# LVMCU.net
KiCad netlist of a schematic drawn in Altium Designer
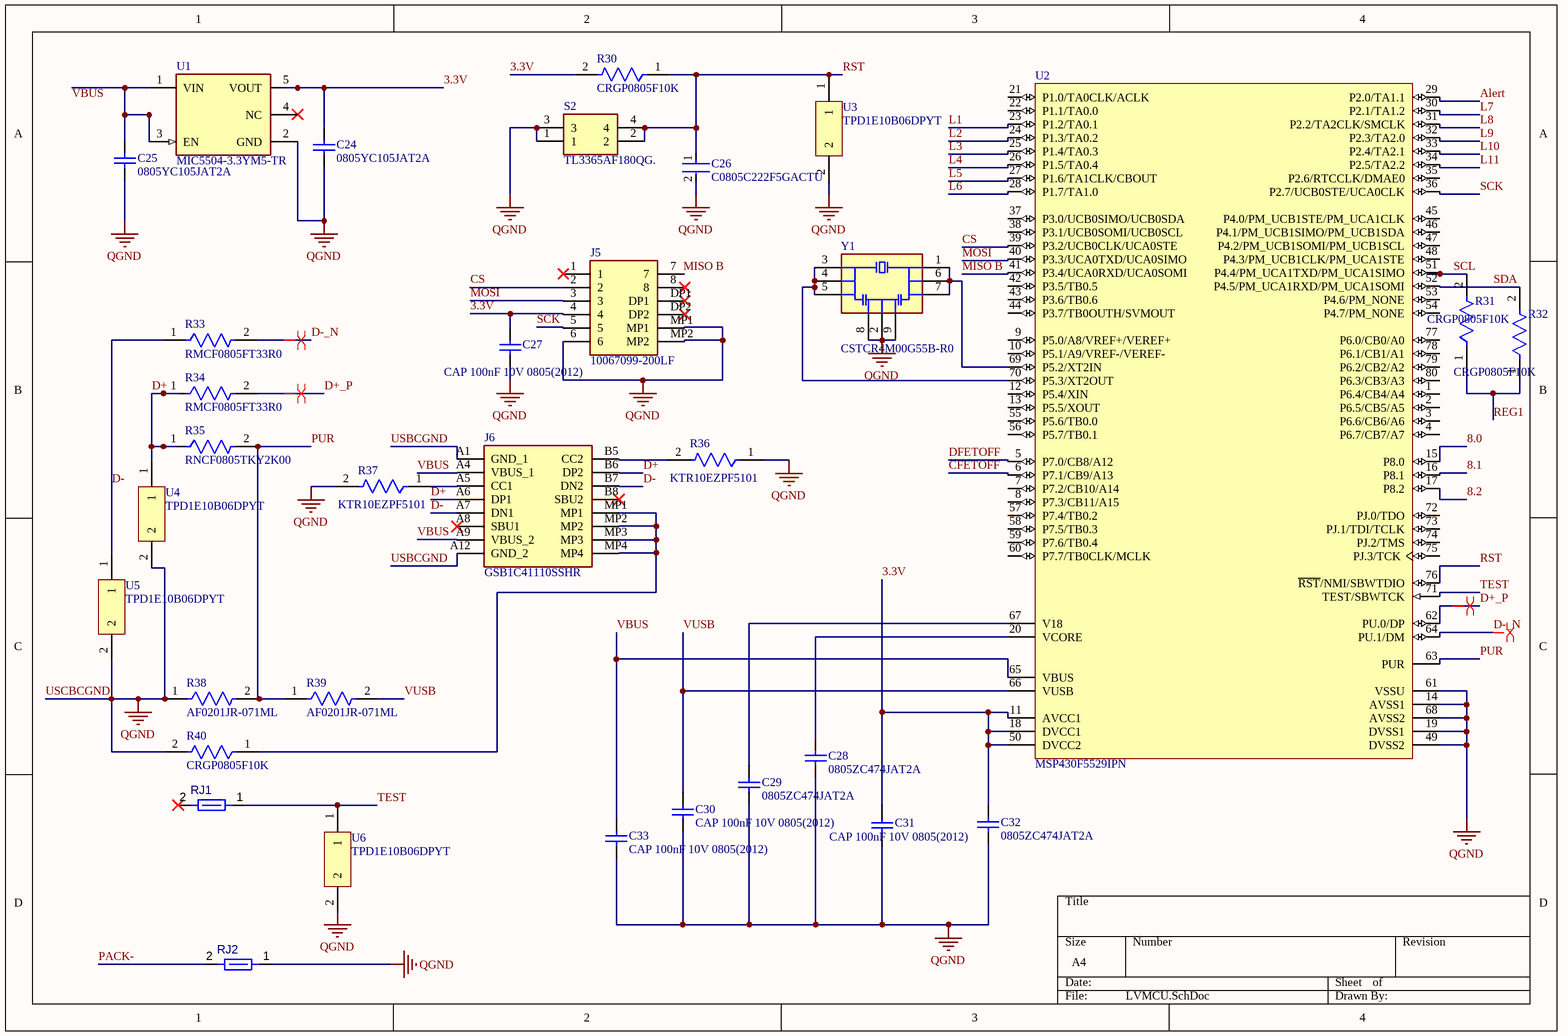
[diagram p0: LVMCU.SchDoc]

(export (version "E")
  (design (tool "Eeschema 10.0.6"))
  (components
    (comp (ref "C24")
      (value "0805YC105JAT2A")
      (footprint "CAPC2013X140X50ML20T25")
      (fields (field (name "MANUFACTURER") "AVX Interconnect / Elco"))
      (libsource (lib "Altium Content Vault") (part "CAP"))
    )
    (comp (ref "C25")
      (value "0805YC105JAT2A")
      (footprint "CAPC2013X140X50ML20T25")
      (fields (field (name "MANUFACTURER") "AVX Interconnect / Elco"))
      (libsource (lib "Altium Content Vault") (part "CAP"))
    )
    (comp (ref "C26")
      (value "C0805C222F5GACTU")
      (footprint "FP-C0805C-DN-MFG")
      (description "CAP CER 2200PF 50V C0G/NP0 0805")
      (fields
        (field (name "OCTOPART") "https://octopart.com/c0805c222f5gactu-kemet-17301038")
        (field (name "TOLERANCE") "0.01")
      )
      (libsource (lib "Altium Content Vault") (part "b4654b650e69147ec39a6b967a45e02"))
    )
    (comp (ref "C27")
      (value "CAP 100nF 10V 0805(2012)")
      (footprint "CAPC0805(2012)100_M")
      (description "CAP 100nF 10V ±5% 0805 (2012 Metric) Thickness 1mm SMD")
      (fields (field (name "TOLERANCE") "Â±5%"))
      (libsource (lib "Altium Content Vault") (part "CAP"))
    )
    (comp (ref "C28")
      (value "0805ZC474JAT2A")
      (footprint "CAPC2013X140X50LL20T25")
      (libsource (lib "Altium Content Vault") (part "CAP"))
    )
    (comp (ref "C29")
      (value "0805ZC474JAT2A")
      (footprint "CAPC2013X140X50LL20T25")
      (libsource (lib "Altium Content Vault") (part "CAP"))
    )
    (comp (ref "C30")
      (value "CAP 100nF 10V 0805(2012)")
      (footprint "CAPC0805(2012)100_M")
      (description "CAP 100nF 10V ±5% 0805 (2012 Metric) Thickness 1mm SMD")
      (fields (field (name "TOLERANCE") "Â±5%"))
      (libsource (lib "Altium Content Vault") (part "CAP"))
    )
    (comp (ref "C31")
      (value "CAP 100nF 10V 0805(2012)")
      (footprint "CAPC0805(2012)100_M")
      (description "CAP 100nF 10V ±5% 0805 (2012 Metric) Thickness 1mm SMD")
      (fields (field (name "TOLERANCE") "Â±5%"))
      (libsource (lib "Altium Content Vault") (part "CAP"))
    )
    (comp (ref "C32")
      (value "0805ZC474JAT2A")
      (footprint "CAPC2013X140X50LL20T25")
      (libsource (lib "Altium Content Vault") (part "CAP"))
    )
    (comp (ref "C33")
      (value "CAP 100nF 10V 0805(2012)")
      (footprint "CAPC0805(2012)100_M")
      (description "CAP 100nF 10V ±5% 0805 (2012 Metric) Thickness 1mm SMD")
      (fields (field (name "TOLERANCE") "Â±5%"))
      (libsource (lib "Altium Content Vault") (part "CAP"))
    )
    (comp (ref "J5")
      (value "10067099-200LF")
      (footprint "SamacSys:10067099200LF")
      (description "Connector")
      (fields (field (name "MOUSER PART NUMBER") "649-10067099-200LF"))
      (libsource (lib "*") (part "10067099-200LF"))
    )
    (comp (ref "J6")
      (value "GSB1C41110SSHR")
      (footprint "SamacSys:GSB1C41110SSHR")
      (description "Connector")
      (libsource (lib "*") (part "GSB1C41110SSHR"))
    )
    (comp (ref "R30")
      (value "CRGP0805F10K")
      (footprint "FP-CRGP0805-IPC_C")
      (description "CRGP0805 10KΩ 0.33W ±100ppm/°C 1% 150V")
      (fields (field (name "OCTOPART") "https://octopart.com/crgp0805f10k-te+connectivity-91018782"))
      (libsource (lib "Altium Content Vault") (part "1029c3af85768c4190bb7ad29bc67b5"))
    )
    (comp (ref "R31")
      (value "CRGP0805F10K")
      (footprint "FP-CRGP0805-IPC_C")
      (description "CRGP0805 10KΩ 0.33W ±100ppm/°C 1% 150V")
      (fields (field (name "OCTOPART") "https://octopart.com/crgp0805f10k-te+connectivity-91018782"))
      (libsource (lib "Altium Content Vault") (part "1029c3af85768c4190bb7ad29bc67b5"))
    )
    (comp (ref "R32")
      (value "CRGP0805F10K")
      (footprint "FP-CRGP0805-IPC_C")
      (description "CRGP0805 10KΩ 0.33W ±100ppm/°C 1% 150V")
      (fields (field (name "OCTOPART") "https://octopart.com/crgp0805f10k-te+connectivity-91018782"))
      (libsource (lib "Altium Content Vault") (part "1029c3af85768c4190bb7ad29bc67b5"))
    )
    (comp (ref "R33")
      (value "RMCF0805FT33R0")
      (footprint "FP-RMCF0805-MFG")
      (description "33Ω ±1% 0.125W 0805 Thick Film Chip Resistor AEC-Q200 compliant")
      (fields (field (name "TOLERANCE") "1%"))
      (libsource (lib "Altium Content Vault") (part "1029c3af85768c4190bb7ad29bc67b5"))
    )
    (comp (ref "R34")
      (value "RMCF0805FT33R0")
      (footprint "FP-RMCF0805-MFG")
      (description "33Ω ±1% 0.125W 0805 Thick Film Chip Resistor AEC-Q200 compliant")
      (fields (field (name "TOLERANCE") "1%"))
      (libsource (lib "Altium Content Vault") (part "1029c3af85768c4190bb7ad29bc67b5"))
    )
    (comp (ref "R35")
      (value "RNCF0805TKY2K00")
      (footprint "FP-RNCF0805-MFG")
      (description "RES 2K OHM 0.01% 1/8W 0805")
      (fields (field (name "TOLERANCE") "0.01%"))
      (libsource (lib "Altium Content Vault") (part "1029c3af85768c4190bb7ad29bc67b5"))
    )
    (comp (ref "R36")
      (value "KTR10EZPF5101")
      (footprint "FP-KTR10-MFG")
      (description "Res Thick Film 0805 5.1kΩ 1% 0.125W ±100ppm/°C Automotive Paper T/R")
      (fields (field (name "TOLERANCE") "1%"))
      (libsource (lib "Altium Content Vault") (part "1029c3af85768c4190bb7ad29bc67b5"))
    )
    (comp (ref "R37")
      (value "KTR10EZPF5101")
      (footprint "FP-KTR10-MFG")
      (description "Res Thick Film 0805 5.1kΩ 1% 0.125W ±100ppm/°C Automotive Paper T/R")
      (fields (field (name "TOLERANCE") "1%"))
      (libsource (lib "Altium Content Vault") (part "1029c3af85768c4190bb7ad29bc67b5"))
    )
    (comp (ref "R38")
      (value "AF0201JR-071ML")
      (footprint "FP-AF0201-IPC_B")
      (description "Anti-Sulfurated Chip Resistors Automotive Grade 1MΩ 5% 200ppm/°C 0201")
      (fields (field (name "TOLERANCE") "5%"))
      (libsource (lib "Altium Content Vault") (part "1029c3af85768c4190bb7ad29bc67b5"))
    )
    (comp (ref "R39")
      (value "AF0201JR-071ML")
      (footprint "FP-AF0201-IPC_B")
      (description "Anti-Sulfurated Chip Resistors Automotive Grade 1MΩ 5% 200ppm/°C 0201")
      (fields (field (name "TOLERANCE") "5%"))
      (libsource (lib "Altium Content Vault") (part "1029c3af85768c4190bb7ad29bc67b5"))
    )
    (comp (ref "R40")
      (value "CRGP0805F10K")
      (footprint "FP-CRGP0805-IPC_C")
      (description "CRGP0805 10KΩ 0.33W ±100ppm/°C 1% 150V")
      (fields (field (name "OCTOPART") "https://octopart.com/crgp0805f10k-te+connectivity-91018782"))
      (libsource (lib "Altium Content Vault") (part "1029c3af85768c4190bb7ad29bc67b5"))
    )
    (comp (ref "RJ1")
      (value "Net Tie 0.6x1.4mm")
      (footprint "SHORT10_8MIL-FP")
      (libsource (lib "Toronto Met Formula Racing") (part "CMP-00022-00002-2"))
    )
    (comp (ref "RJ2")
      (value "Net Tie 0.6x1.4mm")
      (footprint "SHORT10_8MIL-FP")
      (libsource (lib "Toronto Met Formula Racing") (part "CMP-00022-00002-2"))
    )
    (comp (ref "S2")
      (value "TL3365AF180QG.")
      (footprint "SamacSys:TL3365AF180QG")
      (description "Switch")
      (libsource (lib "*") (part "TL3365AF180QG."))
    )
    (comp (ref "U1")
      (value "MIC5504-3.3YM5-TR")
      (footprint "FP-SOT23-5LD-PL-1-MFG")
      (description "IC REG LINEAR 3.3V 300MA SOT23-5")
      (libsource (lib "Altium Content Vault") (part "96048095611b4a9579e1e315950d302"))
    )
    (comp (ref "U2")
      (value "MSP430F5529IPN")
      (footprint "PN0080A_L")
      (libsource (lib "Altium Content Vault") (part "TI-MSP430F552X_A-PN80"))
    )
    (comp (ref "U3")
      (value "TPD1E10B06DPYT")
      (footprint "DPY0002A_L")
      (libsource (lib "Altium Content Vault") (part "TI-TPD1E10B06-X2SON_DPY-2"))
    )
    (comp (ref "U4")
      (value "TPD1E10B06DPYT")
      (footprint "DPY0002A_L")
      (libsource (lib "Altium Content Vault") (part "TI-TPD1E10B06-X2SON_DPY-2"))
    )
    (comp (ref "U5")
      (value "TPD1E10B06DPYT")
      (footprint "DPY0002A_L")
      (libsource (lib "Altium Content Vault") (part "TI-TPD1E10B06-X2SON_DPY-2"))
    )
    (comp (ref "U6")
      (value "TPD1E10B06DPYT")
      (footprint "DPY0002A_L")
      (libsource (lib "Altium Content Vault") (part "TI-TPD1E10B06-X2SON_DPY-2"))
    )
    (comp (ref "Y1")
      (value "CSTCR4M00G55B-R0")
      (footprint "SamacSys:CSTCR4M00G55B95R0")
      (description "Crystal or Oscillator")
      (fields (field (name "MOUSER PART NUMBER") "81-CSTCR4M00G55B-R0"))
      (libsource (lib "*") (part "CSTCR4M00G55B-R0"))
    )
  )
  (nets
    (net (code "1") (name "/3.3V") (class "Default")
      (node (ref "C24") (pin "2") (pinfunction "2_2") (pintype "passive"))
      (node (ref "C27") (pin "2") (pinfunction "2_2") (pintype "passive"))
      (node (ref "C31") (pin "2") (pinfunction "2_2") (pintype "passive"))
      (node (ref "C32") (pin "2") (pinfunction "2_2") (pintype "passive"))
      (node (ref "J5") (pin "4") (pinfunction "4_4") (pintype "passive"))
      (node (ref "R30") (pin "2") (pinfunction "2_2") (pintype "passive"))
      (node (ref "U1") (pin "5") (pinfunction "VOUT_5") (pintype "power_in"))
      (node (ref "U2") (pin "11") (pinfunction "AVCC1_11") (pintype "power_in"))
      (node (ref "U2") (pin "18") (pinfunction "DVCC1_18") (pintype "power_in"))
      (node (ref "U2") (pin "50") (pinfunction "DVCC2_50") (pintype "power_in"))
    )
    (net (code "2") (name "/8.0") (class "Default")
      (node (ref "U2") (pin "15") (pinfunction "P8.0_15") (pintype "bidirectional"))
    )
    (net (code "3") (name "/8.1") (class "Default")
      (node (ref "U2") (pin "16") (pinfunction "P8.1_16") (pintype "bidirectional"))
    )
    (net (code "4") (name "/8.2") (class "Default")
      (node (ref "U2") (pin "17") (pinfunction "P8.2_17") (pintype "bidirectional"))
    )
    (net (code "5") (name "/Alert") (class "Default")
      (node (ref "U2") (pin "29") (pinfunction "P2.0/TA1.1_29") (pintype "bidirectional"))
    )
    (net (code "6") (name "/CFETOFF") (class "Default")
      (node (ref "U2") (pin "6") (pinfunction "P7.1/CB9/A13_6") (pintype "bidirectional"))
    )
    (net (code "7") (name "/CS") (class "Default")
      (node (ref "J5") (pin "2") (pinfunction "2_2") (pintype "passive"))
      (node (ref "U2") (pin "39") (pinfunction "P3.2/UCB0CLK/UCA0STE_39") (pintype "bidirectional"))
    )
    (net (code "8") (name "/D+") (class "Default")
      (node (ref "J6") (pin "A6") (pinfunction "DP1_A6") (pintype "passive"))
      (node (ref "J6") (pin "B6") (pinfunction "DP2_B6") (pintype "passive"))
      (node (ref "R34") (pin "1") (pinfunction "1_1") (pintype "passive"))
      (node (ref "R35") (pin "1") (pinfunction "1_1") (pintype "passive"))
      (node (ref "U4") (pin "1") (pinfunction "1_1") (pintype "passive"))
    )
    (net (code "9") (name "/D+_P") (class "Default")
      (node (ref "R34") (pin "2") (pinfunction "2_2") (pintype "passive"))
      (node (ref "U2") (pin "62") (pinfunction "PU.0/DP_62") (pintype "bidirectional"))
    )
    (net (code "10") (name "/D-") (class "Default")
      (node (ref "J6") (pin "A7") (pinfunction "DN1_A7") (pintype "passive"))
      (node (ref "J6") (pin "B7") (pinfunction "DN2_B7") (pintype "passive"))
      (node (ref "R33") (pin "1") (pinfunction "1_1") (pintype "passive"))
      (node (ref "U5") (pin "1") (pinfunction "1_1") (pintype "passive"))
    )
    (net (code "11") (name "/D-_N") (class "Default")
      (node (ref "R33") (pin "2") (pinfunction "2_2") (pintype "passive"))
      (node (ref "U2") (pin "64") (pinfunction "PU.1/DM_64") (pintype "bidirectional"))
    )
    (net (code "12") (name "/DFETOFF") (class "Default")
      (node (ref "U2") (pin "5") (pinfunction "P7.0/CB8/A12_5") (pintype "bidirectional"))
    )
    (net (code "13") (name "/L1") (class "Default")
      (node (ref "U2") (pin "23") (pinfunction "P1.2/TA0.1_23") (pintype "bidirectional"))
    )
    (net (code "14") (name "/L2") (class "Default")
      (node (ref "U2") (pin "24") (pinfunction "P1.3/TA0.2_24") (pintype "bidirectional"))
    )
    (net (code "15") (name "/L3") (class "Default")
      (node (ref "U2") (pin "25") (pinfunction "P1.4/TA0.3_25") (pintype "bidirectional"))
    )
    (net (code "16") (name "/L4") (class "Default")
      (node (ref "U2") (pin "26") (pinfunction "P1.5/TA0.4_26") (pintype "bidirectional"))
    )
    (net (code "17") (name "/L5") (class "Default")
      (node (ref "U2") (pin "27") (pinfunction "P1.6/TA1CLK/CBOUT_27") (pintype "bidirectional"))
    )
    (net (code "18") (name "/L6") (class "Default")
      (node (ref "U2") (pin "28") (pinfunction "P1.7/TA1.0_28") (pintype "bidirectional"))
    )
    (net (code "19") (name "/L7") (class "Default")
      (node (ref "U2") (pin "30") (pinfunction "P2.1/TA1.2_30") (pintype "bidirectional"))
    )
    (net (code "20") (name "/L8") (class "Default")
      (node (ref "U2") (pin "31") (pinfunction "P2.2/TA2CLK/SMCLK_31") (pintype "bidirectional"))
    )
    (net (code "21") (name "/L9") (class "Default")
      (node (ref "U2") (pin "32") (pinfunction "P2.3/TA2.0_32") (pintype "bidirectional"))
    )
    (net (code "22") (name "/L10") (class "Default")
      (node (ref "U2") (pin "33") (pinfunction "P2.4/TA2.1_33") (pintype "bidirectional"))
    )
    (net (code "23") (name "/L11") (class "Default")
      (node (ref "U2") (pin "34") (pinfunction "P2.5/TA2.2_34") (pintype "bidirectional"))
    )
    (net (code "24") (name "/MISO B") (class "Default")
      (node (ref "J5") (pin "7") (pinfunction "7_7") (pintype "passive"))
      (node (ref "U2") (pin "41") (pinfunction "P3.4/UCA0RXD/UCA0SOMI_41") (pintype "bidirectional"))
    )
    (net (code "25") (name "/MOSI") (class "Default")
      (node (ref "J5") (pin "3") (pinfunction "3_3") (pintype "passive"))
      (node (ref "U2") (pin "40") (pinfunction "P3.3/UCA0TXD/UCA0SIMO_40") (pintype "bidirectional"))
    )
    (net (code "26") (name "/PACK-") (class "Default")
      (node (ref "RJ2") (pin "2") (pinfunction "2_2") (pintype "passive"))
    )
    (net (code "27") (name "/PUR") (class "Default")
      (node (ref "R35") (pin "2") (pinfunction "2_2") (pintype "passive"))
      (node (ref "R38") (pin "2") (pinfunction "2_2") (pintype "passive"))
      (node (ref "R39") (pin "1") (pinfunction "1_1") (pintype "passive"))
      (node (ref "U2") (pin "63") (pinfunction "PUR_63") (pintype "passive"))
    )
    (net (code "28") (name "/REG1") (class "Default")
      (node (ref "R31") (pin "1") (pinfunction "1_1") (pintype "passive"))
      (node (ref "R32") (pin "1") (pinfunction "1_1") (pintype "passive"))
    )
    (net (code "29") (name "/RST") (class "Default")
      (node (ref "C26") (pin "1") (pinfunction "1_1") (pintype "passive"))
      (node (ref "R30") (pin "1") (pinfunction "1_1") (pintype "passive"))
      (node (ref "S2") (pin "2") (pinfunction "2_2") (pintype "passive"))
      (node (ref "S2") (pin "4") (pinfunction "4_4") (pintype "passive"))
      (node (ref "U2") (pin "76") (pinfunction "~{RST}/NMI/SBWTDIO_76") (pintype "bidirectional"))
      (node (ref "U3") (pin "1") (pinfunction "1_1") (pintype "passive"))
    )
    (net (code "30") (name "/SCK") (class "Default")
      (node (ref "J5") (pin "5") (pinfunction "5_5") (pintype "passive"))
      (node (ref "U2") (pin "36") (pinfunction "P2.7/UCB0STE/UCA0CLK_36") (pintype "bidirectional"))
    )
    (net (code "31") (name "/SCL") (class "Default")
      (node (ref "R31") (pin "2") (pinfunction "2_2") (pintype "passive"))
      (node (ref "U2") (pin "51") (pinfunction "P4.4/PM_UCA1TXD/PM_UCA1SIMO_51") (pintype "bidirectional"))
    )
    (net (code "32") (name "/SDA") (class "Default")
      (node (ref "R32") (pin "2") (pinfunction "2_2") (pintype "passive"))
      (node (ref "U2") (pin "52") (pinfunction "P4.5/PM_UCA1RXD/PM_UCA1SOMI_52") (pintype "bidirectional"))
    )
    (net (code "33") (name "/TEST") (class "Default")
      (node (ref "RJ1") (pin "1") (pinfunction "1_1") (pintype "passive"))
      (node (ref "U2") (pin "71") (pinfunction "TEST/SBWTCK_71") (pintype "input"))
      (node (ref "U6") (pin "1") (pinfunction "1_1") (pintype "passive"))
    )
    (net (code "34") (name "/USBCGND") (class "Default")
      (node (ref "J6") (pin "A1") (pinfunction "GND_1_A1") (pintype "passive"))
      (node (ref "J6") (pin "A12") (pinfunction "GND_2_A12") (pintype "passive"))
    )
    (net (code "35") (name "/VBUS") (class "Default")
      (node (ref "C33") (pin "2") (pinfunction "2_2") (pintype "passive"))
      (node (ref "J6") (pin "A4") (pinfunction "VBUS_1_A4") (pintype "passive"))
      (node (ref "J6") (pin "A9") (pinfunction "VBUS_2_A9") (pintype "passive"))
      (node (ref "U2") (pin "65") (pinfunction "VBUS_65") (pintype "power_in"))
    )
    (net (code "36") (name "/VUSB") (class "Default")
      (node (ref "C30") (pin "2") (pinfunction "2_2") (pintype "passive"))
      (node (ref "R39") (pin "2") (pinfunction "2_2") (pintype "passive"))
      (node (ref "U2") (pin "66") (pinfunction "VUSB_66") (pintype "power_in"))
    )
    (net (code "37") (name "Net-(J6-CC1)") (class "Default")
      (node (ref "J6") (pin "A5") (pinfunction "CC1_A5") (pintype "passive"))
      (node (ref "R37") (pin "1") (pinfunction "1_1") (pintype "passive"))
    )
    (net (code "38") (name "Net-(J6-CC2)") (class "Default")
      (node (ref "J6") (pin "B5") (pinfunction "CC2_B5") (pintype "passive"))
      (node (ref "R36") (pin "2") (pinfunction "2_2") (pintype "passive"))
    )
    (net (code "39") (name "Net-(J6-PadMP1)") (class "Default")
      (node (ref "J6") (pin "MP1") (pinfunction "MP1_MP1") (pintype "passive"))
      (node (ref "J6") (pin "MP2") (pinfunction "MP2_MP2") (pintype "passive"))
      (node (ref "J6") (pin "MP3") (pinfunction "MP3_MP3") (pintype "passive"))
      (node (ref "J6") (pin "MP4") (pinfunction "MP4_MP4") (pintype "passive"))
      (node (ref "R40") (pin "1") (pinfunction "1_1") (pintype "passive"))
    )
    (net (code "40") (name "Net-(U1-EN)") (class "Default")
      (node (ref "C25") (pin "2") (pinfunction "2_2") (pintype "passive"))
      (node (ref "U1") (pin "1") (pinfunction "VIN_1") (pintype "power_in"))
      (node (ref "U1") (pin "3") (pinfunction "EN_3") (pintype "input"))
    )
    (net (code "41") (name "Net-(U2-P5.2{slash}XT2IN)") (class "Default")
      (node (ref "U2") (pin "69") (pinfunction "P5.2/XT2IN_69") (pintype "bidirectional"))
      (node (ref "Y1") (pin "1") (pinfunction "INPUT_1_1") (pintype "passive"))
      (node (ref "Y1") (pin "6") (pinfunction "OUTPUT_2_6") (pintype "passive"))
      (node (ref "Y1") (pin "7") (pinfunction "INPUT_3_7") (pintype "passive"))
    )
    (net (code "42") (name "Net-(U2-P5.3{slash}XT2OUT)") (class "Default")
      (node (ref "U2") (pin "70") (pinfunction "P5.3/XT2OUT_70") (pintype "bidirectional"))
      (node (ref "Y1") (pin "3") (pinfunction "OUTPUT_1_3") (pintype "passive"))
      (node (ref "Y1") (pin "4") (pinfunction "INPUT_2_4") (pintype "passive"))
      (node (ref "Y1") (pin "5") (pinfunction "GND_2_5") (pintype "passive"))
    )
    (net (code "43") (name "Net-(U2-V18)") (class "Default")
      (node (ref "C29") (pin "2") (pinfunction "2_2") (pintype "passive"))
      (node (ref "U2") (pin "67") (pinfunction "V18_67") (pintype "passive"))
    )
    (net (code "44") (name "Net-(U2-VCORE)") (class "Default")
      (node (ref "C28") (pin "2") (pinfunction "2_2") (pintype "passive"))
      (node (ref "U2") (pin "20") (pinfunction "VCORE_20") (pintype "passive"))
    )
    (net (code "45") (name "QGND") (class "Default")
      (node (ref "C24") (pin "1") (pinfunction "1_1") (pintype "passive"))
      (node (ref "C25") (pin "1") (pinfunction "1_1") (pintype "passive"))
      (node (ref "C26") (pin "2") (pinfunction "2_2") (pintype "passive"))
      (node (ref "C27") (pin "1") (pinfunction "1_1") (pintype "passive"))
      (node (ref "C28") (pin "1") (pinfunction "1_1") (pintype "passive"))
      (node (ref "C29") (pin "1") (pinfunction "1_1") (pintype "passive"))
      (node (ref "C30") (pin "1") (pinfunction "1_1") (pintype "passive"))
      (node (ref "C31") (pin "1") (pinfunction "1_1") (pintype "passive"))
      (node (ref "C32") (pin "1") (pinfunction "1_1") (pintype "passive"))
      (node (ref "C33") (pin "1") (pinfunction "1_1") (pintype "passive"))
      (node (ref "J5") (pin "6") (pinfunction "6_6") (pintype "passive"))
      (node (ref "J5") (pin "MP1") (pinfunction "MP1_MP1") (pintype "passive"))
      (node (ref "J5") (pin "MP2") (pinfunction "MP2_MP2") (pintype "passive"))
      (node (ref "R36") (pin "1") (pinfunction "1_1") (pintype "passive"))
      (node (ref "R37") (pin "2") (pinfunction "2_2") (pintype "passive"))
      (node (ref "R38") (pin "1") (pinfunction "1_1") (pintype "passive"))
      (node (ref "R40") (pin "2") (pinfunction "2_2") (pintype "passive"))
      (node (ref "RJ2") (pin "1") (pinfunction "1_1") (pintype "passive"))
      (node (ref "S2") (pin "1") (pinfunction "1_1") (pintype "passive"))
      (node (ref "S2") (pin "3") (pinfunction "3_3") (pintype "passive"))
      (node (ref "U1") (pin "2") (pinfunction "GND_2") (pintype "power_in"))
      (node (ref "U2") (pin "14") (pinfunction "AVSS1_14") (pintype "power_in"))
      (node (ref "U2") (pin "19") (pinfunction "DVSS1_19") (pintype "power_in"))
      (node (ref "U2") (pin "49") (pinfunction "DVSS2_49") (pintype "power_in"))
      (node (ref "U2") (pin "61") (pinfunction "VSSU_61") (pintype "power_in"))
      (node (ref "U2") (pin "68") (pinfunction "AVSS2_68") (pintype "power_in"))
      (node (ref "U3") (pin "2") (pinfunction "2_2") (pintype "passive"))
      (node (ref "U4") (pin "2") (pinfunction "2_2") (pintype "passive"))
      (node (ref "U5") (pin "2") (pinfunction "2_2") (pintype "passive"))
      (node (ref "U6") (pin "2") (pinfunction "2_2") (pintype "passive"))
      (node (ref "Y1") (pin "2") (pinfunction "GND_1_2") (pintype "passive"))
      (node (ref "Y1") (pin "8") (pinfunction "GND_3_8") (pintype "passive"))
      (node (ref "Y1") (pin "9") (pinfunction "OUTPUT_3_9") (pintype "passive"))
    )
    (net (code "46") (name "unconnected-(J5-Pad1)") (class "Default")
      (node (ref "J5") (pin "1") (pinfunction "1_1") (pintype "passive+no_connect"))
    )
    (net (code "47") (name "unconnected-(J5-Pad8)") (class "Default")
      (node (ref "J5") (pin "8") (pinfunction "8_8") (pintype "passive+no_connect"))
    )
    (net (code "48") (name "unconnected-(J5-PadDP1)") (class "Default")
      (node (ref "J5") (pin "DP1") (pinfunction "DP1_DP1") (pintype "passive+no_connect"))
    )
    (net (code "49") (name "unconnected-(J5-PadDP2)") (class "Default")
      (node (ref "J5") (pin "DP2") (pinfunction "DP2_DP2") (pintype "passive+no_connect"))
    )
    (net (code "50") (name "unconnected-(J6-SBU1-PadA8)") (class "Default")
      (node (ref "J6") (pin "A8") (pinfunction "SBU1_A8") (pintype "passive+no_connect"))
    )
    (net (code "51") (name "unconnected-(J6-SBU2-PadB8)") (class "Default")
      (node (ref "J6") (pin "B8") (pinfunction "SBU2_B8") (pintype "passive+no_connect"))
    )
    (net (code "52") (name "unconnected-(RJ1-Pad2)") (class "Default")
      (node (ref "RJ1") (pin "2") (pinfunction "2_2") (pintype "passive+no_connect"))
    )
    (net (code "53") (name "unconnected-(U1-NC-Pad4)") (class "Default")
      (node (ref "U1") (pin "4") (pinfunction "NC_4") (pintype "passive"))
    )
    (net (code "54") (name "unconnected-(U2-P1.0{slash}TA0CLK{slash}ACLK-Pad21)") (class "Default")
      (node (ref "U2") (pin "21") (pinfunction "P1.0/TA0CLK/ACLK_21") (pintype "bidirectional"))
    )
    (net (code "55") (name "unconnected-(U2-P1.1{slash}TA0.0-Pad22)") (class "Default")
      (node (ref "U2") (pin "22") (pinfunction "P1.1/TA0.0_22") (pintype "bidirectional"))
    )
    (net (code "56") (name "unconnected-(U2-P2.6{slash}RTCCLK{slash}DMAE0-Pad35)") (class "Default")
      (node (ref "U2") (pin "35") (pinfunction "P2.6/RTCCLK/DMAE0_35") (pintype "bidirectional"))
    )
    (net (code "57") (name "unconnected-(U2-P3.0{slash}UCB0SIMO{slash}UCB0SDA-Pad37)") (class "Default")
      (node (ref "U2") (pin "37") (pinfunction "P3.0/UCB0SIMO/UCB0SDA_37") (pintype "bidirectional"))
    )
    (net (code "58") (name "unconnected-(U2-P3.1{slash}UCB0SOMI{slash}UCB0SCL-Pad38)") (class "Default")
      (node (ref "U2") (pin "38") (pinfunction "P3.1/UCB0SOMI/UCB0SCL_38") (pintype "bidirectional"))
    )
    (net (code "59") (name "unconnected-(U2-P3.5{slash}TB0.5-Pad42)") (class "Default")
      (node (ref "U2") (pin "42") (pinfunction "P3.5/TB0.5_42") (pintype "bidirectional"))
    )
    (net (code "60") (name "unconnected-(U2-P3.6{slash}TB0.6-Pad43)") (class "Default")
      (node (ref "U2") (pin "43") (pinfunction "P3.6/TB0.6_43") (pintype "bidirectional"))
    )
    (net (code "61") (name "unconnected-(U2-P3.7{slash}TB0OUTH{slash}SVMOUT-Pad44)") (class "Default")
      (node (ref "U2") (pin "44") (pinfunction "P3.7/TB0OUTH/SVMOUT_44") (pintype "bidirectional"))
    )
    (net (code "62") (name "unconnected-(U2-P4.0{slash}PM_UCB1STE{slash}PM_UCA1CLK-Pad45)") (class "Default")
      (node (ref "U2") (pin "45") (pinfunction "P4.0/PM_UCB1STE/PM_UCA1CLK_45") (pintype "bidirectional"))
    )
    (net (code "63") (name "unconnected-(U2-P4.1{slash}PM_UCB1SIMO{slash}PM_UCB1SDA-Pad46)") (class "Default")
      (node (ref "U2") (pin "46") (pinfunction "P4.1/PM_UCB1SIMO/PM_UCB1SDA_46") (pintype "bidirectional"))
    )
    (net (code "64") (name "unconnected-(U2-P4.2{slash}PM_UCB1SOMI{slash}PM_UCB1SCL-Pad47)") (class "Default")
      (node (ref "U2") (pin "47") (pinfunction "P4.2/PM_UCB1SOMI/PM_UCB1SCL_47") (pintype "bidirectional"))
    )
    (net (code "65") (name "unconnected-(U2-P4.3{slash}PM_UCB1CLK{slash}PM_UCA1STE-Pad48)") (class "Default")
      (node (ref "U2") (pin "48") (pinfunction "P4.3/PM_UCB1CLK/PM_UCA1STE_48") (pintype "bidirectional"))
    )
    (net (code "66") (name "unconnected-(U2-P4.6{slash}PM_NONE-Pad53)") (class "Default")
      (node (ref "U2") (pin "53") (pinfunction "P4.6/PM_NONE_53") (pintype "bidirectional"))
    )
    (net (code "67") (name "unconnected-(U2-P4.7{slash}PM_NONE-Pad54)") (class "Default")
      (node (ref "U2") (pin "54") (pinfunction "P4.7/PM_NONE_54") (pintype "bidirectional"))
    )
    (net (code "68") (name "unconnected-(U2-P5.0{slash}A8{slash}VREF+{slash}VEREF+-Pad9)") (class "Default")
      (node (ref "U2") (pin "9") (pinfunction "P5.0/A8/VREF+/VEREF+_9") (pintype "bidirectional"))
    )
    (net (code "69") (name "unconnected-(U2-P5.1{slash}A9{slash}VREF-{slash}VEREF--Pad10)") (class "Default")
      (node (ref "U2") (pin "10") (pinfunction "P5.1/A9/VREF-/VEREF-_10") (pintype "bidirectional"))
    )
    (net (code "70") (name "unconnected-(U2-P5.4{slash}XIN-Pad12)") (class "Default")
      (node (ref "U2") (pin "12") (pinfunction "P5.4/XIN_12") (pintype "bidirectional"))
    )
    (net (code "71") (name "unconnected-(U2-P5.5{slash}XOUT-Pad13)") (class "Default")
      (node (ref "U2") (pin "13") (pinfunction "P5.5/XOUT_13") (pintype "bidirectional"))
    )
    (net (code "72") (name "unconnected-(U2-P5.6{slash}TB0.0-Pad55)") (class "Default")
      (node (ref "U2") (pin "55") (pinfunction "P5.6/TB0.0_55") (pintype "bidirectional"))
    )
    (net (code "73") (name "unconnected-(U2-P5.7{slash}TB0.1-Pad56)") (class "Default")
      (node (ref "U2") (pin "56") (pinfunction "P5.7/TB0.1_56") (pintype "bidirectional"))
    )
    (net (code "74") (name "unconnected-(U2-P6.0{slash}CB0{slash}A0-Pad77)") (class "Default")
      (node (ref "U2") (pin "77") (pinfunction "P6.0/CB0/A0_77") (pintype "bidirectional"))
    )
    (net (code "75") (name "unconnected-(U2-P6.1{slash}CB1{slash}A1-Pad78)") (class "Default")
      (node (ref "U2") (pin "78") (pinfunction "P6.1/CB1/A1_78") (pintype "bidirectional"))
    )
    (net (code "76") (name "unconnected-(U2-P6.2{slash}CB2{slash}A2-Pad79)") (class "Default")
      (node (ref "U2") (pin "79") (pinfunction "P6.2/CB2/A2_79") (pintype "bidirectional"))
    )
    (net (code "77") (name "unconnected-(U2-P6.3{slash}CB3{slash}A3-Pad80)") (class "Default")
      (node (ref "U2") (pin "80") (pinfunction "P6.3/CB3/A3_80") (pintype "bidirectional"))
    )
    (net (code "78") (name "unconnected-(U2-P6.4{slash}CB4{slash}A4-Pad1)") (class "Default")
      (node (ref "U2") (pin "1") (pinfunction "P6.4/CB4/A4_1") (pintype "bidirectional"))
    )
    (net (code "79") (name "unconnected-(U2-P6.5{slash}CB5{slash}A5-Pad2)") (class "Default")
      (node (ref "U2") (pin "2") (pinfunction "P6.5/CB5/A5_2") (pintype "bidirectional"))
    )
    (net (code "80") (name "unconnected-(U2-P6.6{slash}CB6{slash}A6-Pad3)") (class "Default")
      (node (ref "U2") (pin "3") (pinfunction "P6.6/CB6/A6_3") (pintype "bidirectional"))
    )
    (net (code "81") (name "unconnected-(U2-P6.7{slash}CB7{slash}A7-Pad4)") (class "Default")
      (node (ref "U2") (pin "4") (pinfunction "P6.7/CB7/A7_4") (pintype "bidirectional"))
    )
    (net (code "82") (name "unconnected-(U2-P7.2{slash}CB10{slash}A14-Pad7)") (class "Default")
      (node (ref "U2") (pin "7") (pinfunction "P7.2/CB10/A14_7") (pintype "bidirectional"))
    )
    (net (code "83") (name "unconnected-(U2-P7.3{slash}CB11{slash}A15-Pad8)") (class "Default")
      (node (ref "U2") (pin "8") (pinfunction "P7.3/CB11/A15_8") (pintype "bidirectional"))
    )
    (net (code "84") (name "unconnected-(U2-P7.4{slash}TB0.2-Pad57)") (class "Default")
      (node (ref "U2") (pin "57") (pinfunction "P7.4/TB0.2_57") (pintype "bidirectional"))
    )
    (net (code "85") (name "unconnected-(U2-P7.5{slash}TB0.3-Pad58)") (class "Default")
      (node (ref "U2") (pin "58") (pinfunction "P7.5/TB0.3_58") (pintype "bidirectional"))
    )
    (net (code "86") (name "unconnected-(U2-P7.6{slash}TB0.4-Pad59)") (class "Default")
      (node (ref "U2") (pin "59") (pinfunction "P7.6/TB0.4_59") (pintype "bidirectional"))
    )
    (net (code "87") (name "unconnected-(U2-P7.7{slash}TB0CLK{slash}MCLK-Pad60)") (class "Default")
      (node (ref "U2") (pin "60") (pinfunction "P7.7/TB0CLK/MCLK_60") (pintype "bidirectional"))
    )
    (net (code "88") (name "unconnected-(U2-PJ.0{slash}TDO-Pad72)") (class "Default")
      (node (ref "U2") (pin "72") (pinfunction "PJ.0/TDO_72") (pintype "bidirectional"))
    )
    (net (code "89") (name "unconnected-(U2-PJ.1{slash}TDI{slash}TCLK-Pad73)") (class "Default")
      (node (ref "U2") (pin "73") (pinfunction "PJ.1/TDI/TCLK_73") (pintype "bidirectional"))
    )
    (net (code "90") (name "unconnected-(U2-PJ.2{slash}TMS-Pad74)") (class "Default")
      (node (ref "U2") (pin "74") (pinfunction "PJ.2/TMS_74") (pintype "bidirectional"))
    )
    (net (code "91") (name "unconnected-(U2-PJ.3{slash}TCK-Pad75)") (class "Default")
      (node (ref "U2") (pin "75") (pinfunction "PJ.3/TCK_75") (pintype "bidirectional"))
    )
  )
)
